# USB-UART_1_0.net
KiCad netlist of a schematic drawn in Altium Designer
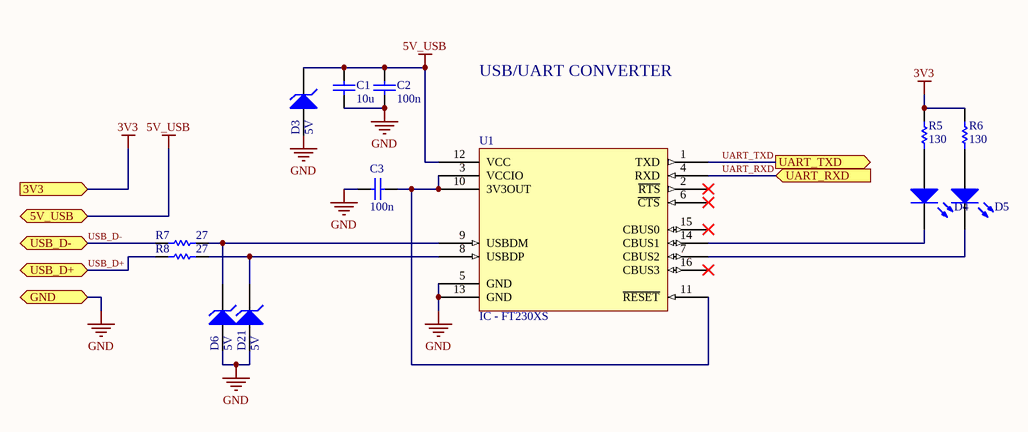
[diagram p0: USB-UART_1.0.SchDoc]

(export (version "E")
  (design (tool "Eeschema 10.0.6"))
  (components
    (comp (ref "C1")
      (value "10u")
      (footprint "CS-0603")
      (fields
        (field (name "TOLERANCE") "10%")
        (field (name "VOLTAGE") "16V")
        (field (name "Comment") "CS - CAPACITOR")
      )
      (libsource (lib "CHINOOK_LIBRARY") (part "CS - CAPACITOR"))
    )
    (comp (ref "C2")
      (value "100n")
      (footprint "CS-0603")
      (fields
        (field (name "TOLERANCE") "10%")
        (field (name "VOLTAGE") "16V")
        (field (name "Comment") "CS - CAPACITOR")
      )
      (libsource (lib "CHINOOK_LIBRARY") (part "CS - CAPACITOR"))
    )
    (comp (ref "C3")
      (value "100n")
      (footprint "CS-0603")
      (fields
        (field (name "TOLERANCE") "10%")
        (field (name "VOLTAGE") "16V")
        (field (name "Comment") "CS - CAPACITOR")
      )
      (libsource (lib "CHINOOK_LIBRARY") (part "CS - CAPACITOR"))
    )
    (comp (ref "D3")
      (value "DS - TVS ESD5Z5.0T1G")
      (footprint "DS-SOD523")
      (description "TVS 5V")
      (fields
        (field (name "MANUFACTURER") "ON Semiconductor")
        (field (name "VOLTAGE - REVERSE STANDOFF (TYP)") "5V")
      )
      (libsource (lib "CHINOOK_LIBRARY") (part "DS - TVS ESD5Z5.0T1G"))
    )
    (comp (ref "D4")
      (value "LED - NORMAL LED")
      (footprint "LED-0603 BLUE")
      (libsource (lib "CHINOOK_LIBRARY") (part "LED - NORMAL LED"))
    )
    (comp (ref "D5")
      (value "LED - NORMAL LED")
      (footprint "LED-0603 BLUE")
      (libsource (lib "CHINOOK_LIBRARY") (part "LED - NORMAL LED"))
    )
    (comp (ref "D6")
      (value "DS - TVS ESD5Z5.0T1G")
      (footprint "DS-SOD523")
      (description "TVS 5V")
      (fields
        (field (name "MANUFACTURER") "ON Semiconductor")
        (field (name "VOLTAGE - REVERSE STANDOFF (TYP)") "5V")
      )
      (libsource (lib "CHINOOK_LIBRARY") (part "DS - TVS ESD5Z5.0T1G"))
    )
    (comp (ref "D21")
      (value "DS - TVS ESD5Z5.0T1G")
      (footprint "DS-SOD523")
      (description "TVS 5V")
      (fields
        (field (name "MANUFACTURER") "ON Semiconductor")
        (field (name "VOLTAGE - REVERSE STANDOFF (TYP)") "5V")
      )
      (libsource (lib "CHINOOK_LIBRARY") (part "DS - TVS ESD5Z5.0T1G"))
    )
    (comp (ref "R5")
      (value "130")
      (footprint "RS-0603")
      (fields
        (field (name "TOLERANCE") "RES TOL")
        (field (name "POWER") "RES POWER")
        (field (name "Comment") "RS - RESISTOR")
      )
      (libsource (lib "CHINOOK_LIBRARY") (part "RS - RESISTOR"))
    )
    (comp (ref "R6")
      (value "130")
      (footprint "RS-0603")
      (fields
        (field (name "TOLERANCE") "RES TOL")
        (field (name "POWER") "RES POWER")
        (field (name "Comment") "RS - RESISTOR")
      )
      (libsource (lib "CHINOOK_LIBRARY") (part "RS - RESISTOR"))
    )
    (comp (ref "R7")
      (value "27")
      (footprint "RS-0603")
      (fields
        (field (name "TOLERANCE") "RES TOL")
        (field (name "POWER") "RES POWER")
        (field (name "Comment") "RS - RESISTOR")
      )
      (libsource (lib "CHINOOK_LIBRARY") (part "RS - RESISTOR"))
    )
    (comp (ref "R8")
      (value "27")
      (footprint "RS-0603")
      (fields
        (field (name "TOLERANCE") "RES TOL")
        (field (name "POWER") "RES POWER")
        (field (name "Comment") "RS - RESISTOR")
      )
      (libsource (lib "CHINOOK_LIBRARY") (part "RS - RESISTOR"))
    )
    (comp (ref "U1")
      (value "IC - FT230XS")
      (footprint "IC-SSOP-16")
      (description "USB to BASIC UART IC")
      (fields (field (name "MANUFACTURER") "FTDI"))
      (libsource (lib "CHINOOK_LIBRARY") (part "IC - FT230XS"))
    )
  )
  (nets
    (net (code "1") (name "/UART_RXD") (class "Default")
      (node (ref "U1") (pin "4") (pinfunction "RXD_4") (pintype "input"))
    )
    (net (code "2") (name "/UART_TXD") (class "Default")
      (node (ref "U1") (pin "1") (pinfunction "TXD_1") (pintype "output"))
    )
    (net (code "3") (name "/USB_D+") (class "Default")
      (node (ref "R8") (pin "2") (pinfunction "2_2") (pintype "passive"))
    )
    (net (code "4") (name "/USB_D-") (class "Default")
      (node (ref "R7") (pin "2") (pinfunction "2_2") (pintype "passive"))
    )
    (net (code "5") (name "3V3") (class "Default")
      (node (ref "R5") (pin "2") (pinfunction "2_2") (pintype "passive"))
      (node (ref "R6") (pin "2") (pinfunction "2_2") (pintype "passive"))
    )
    (net (code "6") (name "5V_USB") (class "Default")
      (node (ref "C1") (pin "2") (pinfunction "2_2") (pintype "passive"))
      (node (ref "C2") (pin "2") (pinfunction "2_2") (pintype "passive"))
      (node (ref "D3") (pin "K") (pinfunction "K_K") (pintype "passive"))
      (node (ref "U1") (pin "12") (pinfunction "VCC_12") (pintype "power_in"))
    )
    (net (code "7") (name "GND") (class "Default")
      (node (ref "C1") (pin "1") (pinfunction "1_1") (pintype "passive"))
      (node (ref "C2") (pin "1") (pinfunction "1_1") (pintype "passive"))
      (node (ref "C3") (pin "2") (pinfunction "2_2") (pintype "passive"))
      (node (ref "D21") (pin "A") (pinfunction "A_A") (pintype "passive"))
      (node (ref "D3") (pin "A") (pinfunction "A_A") (pintype "passive"))
      (node (ref "D6") (pin "A") (pinfunction "A_A") (pintype "passive"))
      (node (ref "U1") (pin "13") (pinfunction "GND_13") (pintype "power_in"))
      (node (ref "U1") (pin "5") (pinfunction "GND_5") (pintype "power_in"))
    )
    (net (code "8") (name "Net-(D4-PadA)") (class "Default")
      (node (ref "D4") (pin "A") (pinfunction "A_A") (pintype "passive"))
      (node (ref "R5") (pin "1") (pinfunction "1_1") (pintype "passive"))
    )
    (net (code "9") (name "Net-(D5-PadA)") (class "Default")
      (node (ref "D5") (pin "A") (pinfunction "A_A") (pintype "passive"))
      (node (ref "R6") (pin "1") (pinfunction "1_1") (pintype "passive"))
    )
    (net (code "10") (name "Net-(U1-3V3OUT)") (class "Default")
      (node (ref "C3") (pin "1") (pinfunction "1_1") (pintype "passive"))
      (node (ref "U1") (pin "10") (pinfunction "3V3OUT_10") (pintype "power_in"))
      (node (ref "U1") (pin "11") (pinfunction "~{RESET}_11") (pintype "input"))
      (node (ref "U1") (pin "3") (pinfunction "VCCIO_3") (pintype "power_in"))
    )
    (net (code "11") (name "Net-(U1-CBUS1)") (class "Default")
      (node (ref "D4") (pin "K") (pinfunction "K_K") (pintype "passive"))
      (node (ref "U1") (pin "14") (pinfunction "CBUS1_14") (pintype "bidirectional"))
    )
    (net (code "12") (name "Net-(U1-CBUS2)") (class "Default")
      (node (ref "D5") (pin "K") (pinfunction "K_K") (pintype "passive"))
      (node (ref "U1") (pin "7") (pinfunction "CBUS2_7") (pintype "bidirectional"))
    )
    (net (code "13") (name "Net-(U1-USBDM)") (class "Default")
      (node (ref "D6") (pin "K") (pinfunction "K_K") (pintype "passive"))
      (node (ref "R7") (pin "1") (pinfunction "1_1") (pintype "passive"))
      (node (ref "U1") (pin "9") (pinfunction "USBDM_9") (pintype "input"))
    )
    (net (code "14") (name "Net-(U1-USBDP)") (class "Default")
      (node (ref "D21") (pin "K") (pinfunction "K_K") (pintype "passive"))
      (node (ref "R8") (pin "1") (pinfunction "1_1") (pintype "passive"))
      (node (ref "U1") (pin "8") (pinfunction "USBDP_8") (pintype "input"))
    )
    (net (code "15") (name "unconnected-(U1-CBUS0-Pad15)") (class "Default")
      (node (ref "U1") (pin "15") (pinfunction "CBUS0_15") (pintype "bidirectional+no_connect"))
    )
    (net (code "16") (name "unconnected-(U1-CBUS3-Pad16)") (class "Default")
      (node (ref "U1") (pin "16") (pinfunction "CBUS3_16") (pintype "bidirectional+no_connect"))
    )
    (net (code "17") (name "unconnected-(U1-~{CTS}-Pad6)") (class "Default")
      (node (ref "U1") (pin "6") (pinfunction "~{CTS}_6") (pintype "input+no_connect"))
    )
    (net (code "18") (name "unconnected-(U1-~{RTS}-Pad2)") (class "Default")
      (node (ref "U1") (pin "2") (pinfunction "~{RTS}_2") (pintype "output+no_connect"))
    )
  )
)
